# Adafruit_MicroUSB_Lipo.net
KiCad netlist of a schematic drawn in EAGLE
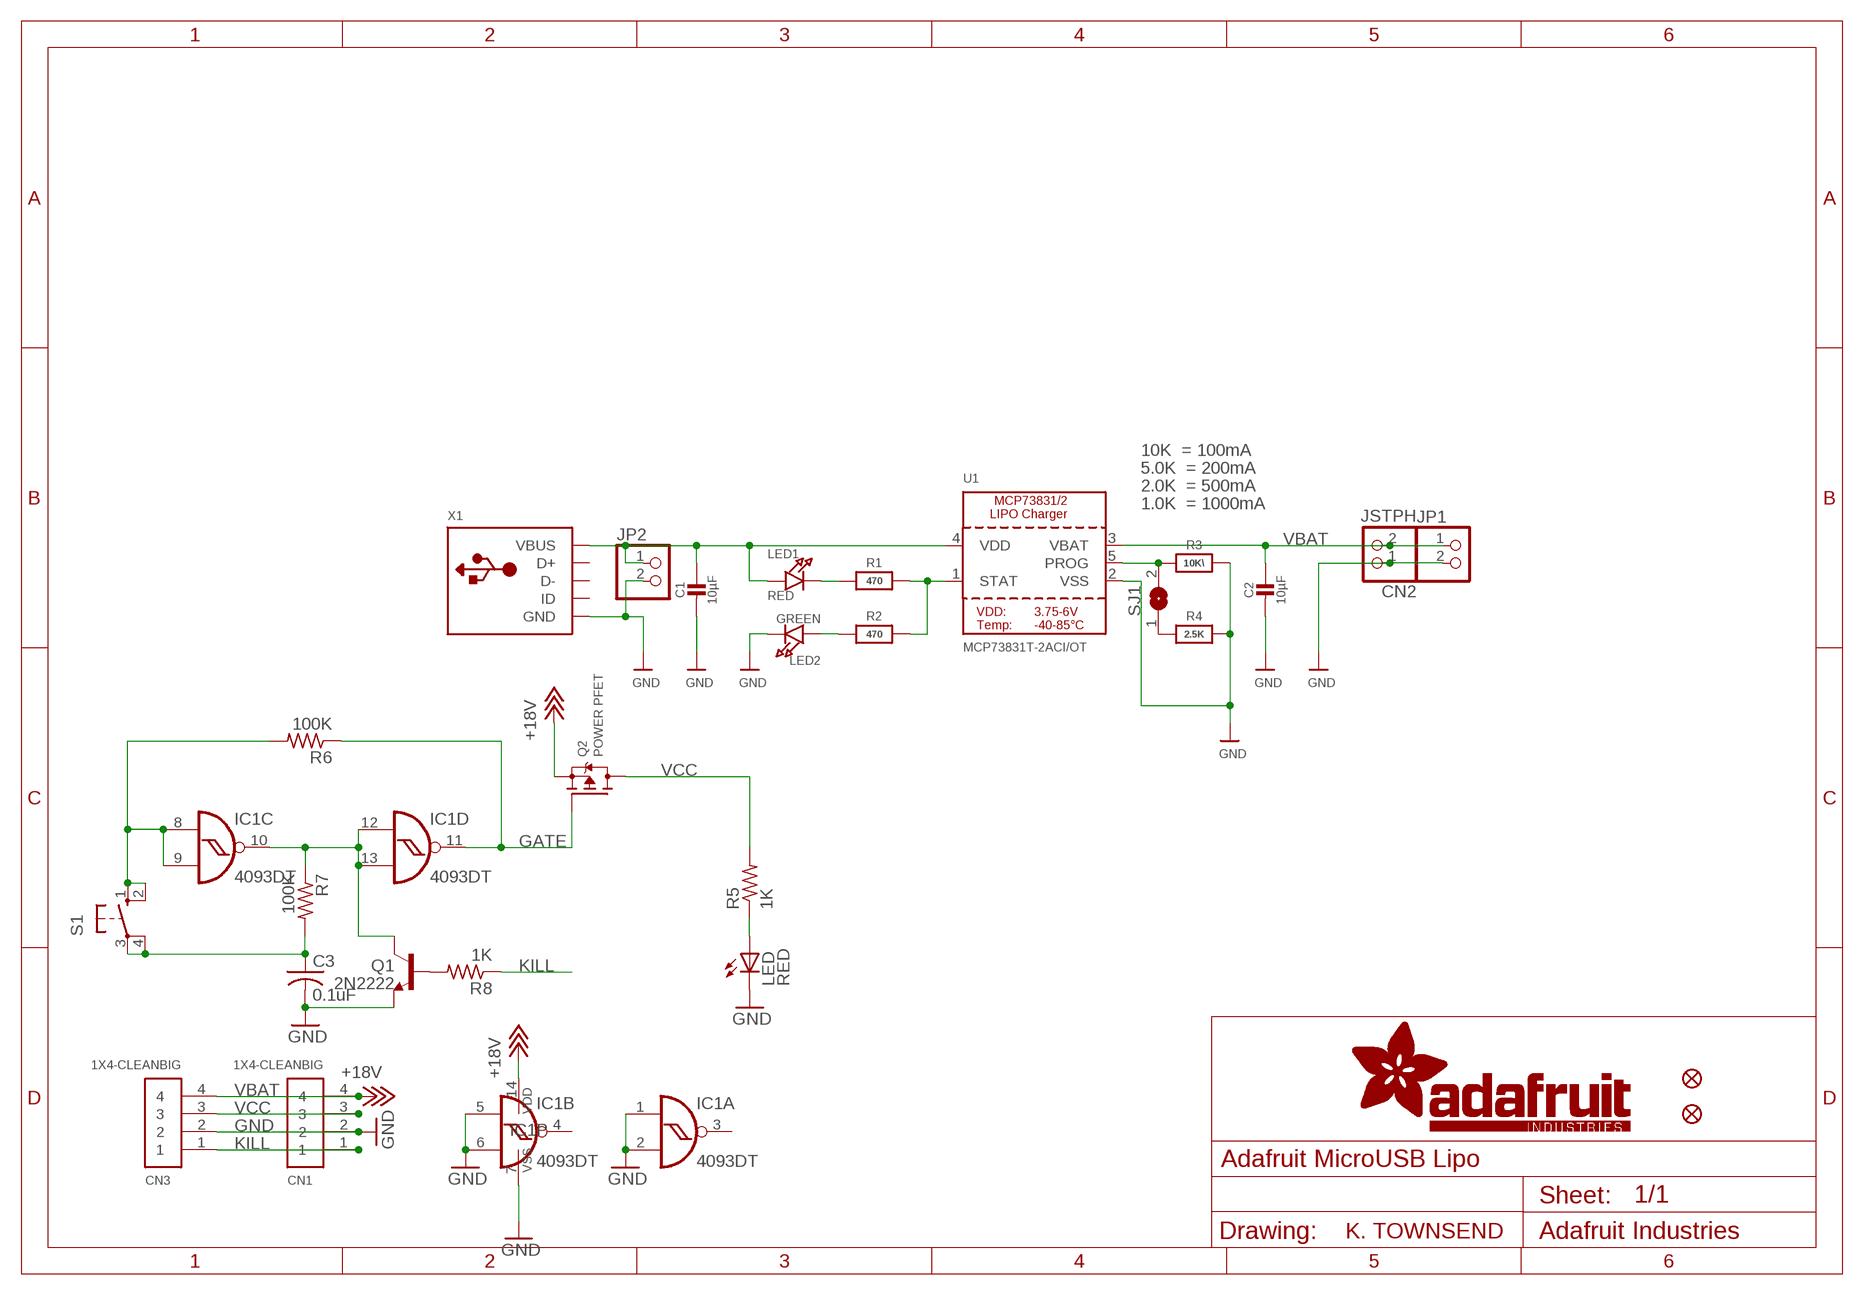
[diagram p0: schematic, sheet 1]

(export (version "E")
  (design (tool "Eeschema 10.0.6"))
  (components
    (comp (ref "C1")
      (value "10µF")
      (footprint "eagle-import:0805-NO")
      (libsource (lib "eagle-import") (part "CAP_CERAMIC0805-NOOUTLINE"))
    )
    (comp (ref "C2")
      (value "10µF")
      (footprint "eagle-import:0805-NO")
      (libsource (lib "eagle-import") (part "CAP_CERAMIC0805-NOOUTLINE"))
    )
    (comp (ref "C3")
      (value "0.1uF")
      (footprint "eagle-import:C0805")
      (libsource (lib "eagle-import") (part "C-USC0805"))
    )
    (comp (ref "CN1")
      (value "1X4-CLEANBIG")
      (footprint "eagle-import:1X04-CLEANBIG")
      (libsource (lib "eagle-import") (part "1X4-CLEANBIG"))
    )
    (comp (ref "CN2")
      (value "JSTPH")
      (footprint "eagle-import:JSTPH2")
      (libsource (lib "eagle-import") (part "JST_2PIN"))
    )
    (comp (ref "CN3")
      (value "1X4-CLEANBIG")
      (footprint "eagle-import:1X04-CLEANBIG")
      (libsource (lib "eagle-import") (part "1X4-CLEANBIG"))
    )
    (comp (ref "FID1")
      (value "FIDUCIAL\"\"")
      (footprint "eagle-import:FIDUCIAL_1MM")
      (libsource (lib "eagle-import") (part "FIDUCIAL{dblquote}{dblquote}"))
    )
    (comp (ref "FID2")
      (value "FIDUCIAL\"\"")
      (footprint "eagle-import:FIDUCIAL_1MM")
      (fields (field (name "BOM") "EXCLUDE"))
      (libsource (lib "eagle-import") (part "FIDUCIAL{dblquote}{dblquote}"))
    )
    (comp (ref "IC1")
      (value "4093DT")
      (footprint "eagle-import:MC14093B-TSSOP14")
      (libsource (lib "eagle-import") (part "4093DT"))
    )
    (comp (ref "JP1")
      (value "HEADER-1X2ROUND")
      (footprint "eagle-import:1X02_ROUND")
      (libsource (lib "eagle-import") (part "HEADER-1X2ROUND"))
    )
    (comp (ref "JP2")
      (value "HEADER-1X2ROUND")
      (footprint "eagle-import:1X02_ROUND")
      (libsource (lib "eagle-import") (part "HEADER-1X2ROUND"))
    )
    (comp (ref "LED")
      (value "RED")
      (footprint "eagle-import:CHIP-LED0805")
      (libsource (lib "eagle-import") (part "LEDCHIP-LED0805"))
    )
    (comp (ref "LED1")
      (value "RED")
      (footprint "eagle-import:CHIPLED_0805_NOOUTLINE")
      (libsource (lib "eagle-import") (part "LED0805_NOOUTLINE"))
    )
    (comp (ref "LED2")
      (value "GREEN")
      (footprint "eagle-import:CHIPLED_0805_NOOUTLINE")
      (libsource (lib "eagle-import") (part "LED0805_NOOUTLINE"))
    )
    (comp (ref "Q1")
      (value "2N2222")
      (footprint "eagle-import:SOT23-BEC")
      (libsource (lib "eagle-import") (part "-NPN-SOT23-BECMMBT2222ALT1"))
    )
    (comp (ref "Q2")
      (value "POWER PFET")
      (footprint "eagle-import:SOT23-WIDE")
      (libsource (lib "eagle-import") (part "MOSFET-PWIDE"))
    )
    (comp (ref "R1")
      (value "470")
      (footprint "eagle-import:0805-NO")
      (libsource (lib "eagle-import") (part "RESISTOR0805_NOOUTLINE"))
    )
    (comp (ref "R2")
      (value "470")
      (footprint "eagle-import:0805-NO")
      (libsource (lib "eagle-import") (part "RESISTOR0805_NOOUTLINE"))
    )
    (comp (ref "R3")
      (value "10K\\")
      (footprint "eagle-import:0805-NO")
      (libsource (lib "eagle-import") (part "RESISTOR0805_NOOUTLINE"))
    )
    (comp (ref "R4")
      (value "2.5K")
      (footprint "eagle-import:0805-NO")
      (libsource (lib "eagle-import") (part "RESISTOR0805_NOOUTLINE"))
    )
    (comp (ref "R5")
      (value "1K")
      (footprint "eagle-import:R0805")
      (libsource (lib "eagle-import") (part "rcl_R-US_R0805"))
    )
    (comp (ref "R6")
      (value "100K")
      (footprint "eagle-import:R0805")
      (libsource (lib "eagle-import") (part "rcl_R-US_R0805"))
    )
    (comp (ref "R7")
      (value "100K")
      (footprint "eagle-import:R0805")
      (libsource (lib "eagle-import") (part "rcl_R-US_R0805"))
    )
    (comp (ref "R8")
      (value "1K")
      (footprint "eagle-import:R0805")
      (libsource (lib "eagle-import") (part "R-US_R0805"))
    )
    (comp (ref "S1")
      (value "40-XX-ROUND")
      (footprint "eagle-import:B3F-40XX-ROUND")
      (libsource (lib "eagle-import") (part "40-XX-ROUND"))
    )
    (comp (ref "SJ1")
      (value "SOLDERJUMPER")
      (footprint "eagle-import:SOLDERJUMPER_ARROW_NOPASTE")
      (libsource (lib "eagle-import") (part "SOLDERJUMPER"))
    )
    (comp (ref "U1")
      (value "MCP73831T-2ACI/OT")
      (footprint "eagle-import:SOT23-5")
      (libsource (lib "eagle-import") (part "MCP73831/2"))
    )
    (comp (ref "X1")
      (value "USBMICRO_20329")
      (footprint "eagle-import:4UCONN_20329")
      (libsource (lib "eagle-import") (part "USBMICRO_20329"))
    )
  )
  (nets
    (net (code "1") (name "+18V") (class "Default")
      (node (ref "C2") (pin "1") (pinfunction "1_1") (pintype "passive"))
      (node (ref "CN1") (pin "4") (pinfunction "4_4") (pintype "bidirectional"))
      (node (ref "CN2") (pin "2") (pinfunction "2_2") (pintype "passive"))
      (node (ref "CN3") (pin "4") (pinfunction "4_4") (pintype "bidirectional"))
      (node (ref "IC1") (pin "14") (pinfunction "VDD_14") (pintype "power_in"))
      (node (ref "JP1") (pin "1") (pinfunction "1_1") (pintype "passive"))
      (node (ref "Q2") (pin "2") (pinfunction "S_2") (pintype "passive"))
      (node (ref "U1") (pin "3") (pinfunction "VBAT_3") (pintype "power_in"))
    )
    (net (code "2") (name "/GATE") (class "Default")
      (node (ref "IC1") (pin "11") (pinfunction "O_11") (pintype "output"))
      (node (ref "Q2") (pin "1") (pinfunction "G_1") (pintype "passive"))
      (node (ref "R6") (pin "1") (pinfunction "1_1") (pintype "passive"))
    )
    (net (code "3") (name "/KILL") (class "Default")
      (node (ref "CN1") (pin "1") (pinfunction "1_1") (pintype "bidirectional"))
      (node (ref "CN3") (pin "1") (pinfunction "1_1") (pintype "bidirectional"))
      (node (ref "R8") (pin "1") (pinfunction "1_1") (pintype "passive"))
    )
    (net (code "4") (name "/VCC") (class "Default")
      (node (ref "CN1") (pin "3") (pinfunction "3_3") (pintype "bidirectional"))
      (node (ref "CN3") (pin "3") (pinfunction "3_3") (pintype "bidirectional"))
      (node (ref "Q2") (pin "3") (pinfunction "D_3") (pintype "passive"))
      (node (ref "R5") (pin "2") (pinfunction "2_2") (pintype "passive"))
    )
    (net (code "5") (name "GND") (class "Default")
      (node (ref "C1") (pin "2") (pinfunction "2_2") (pintype "passive"))
      (node (ref "C2") (pin "2") (pinfunction "2_2") (pintype "passive"))
      (node (ref "C3") (pin "2") (pinfunction "2_2") (pintype "passive"))
      (node (ref "CN1") (pin "2") (pinfunction "2_2") (pintype "bidirectional"))
      (node (ref "CN2") (pin "1") (pinfunction "1_1") (pintype "passive"))
      (node (ref "CN3") (pin "2") (pinfunction "2_2") (pintype "bidirectional"))
      (node (ref "IC1") (pin "1") (pinfunction "I0_1") (pintype "input"))
      (node (ref "IC1") (pin "2") (pinfunction "I1_2") (pintype "input"))
      (node (ref "IC1") (pin "5") (pinfunction "I0_5") (pintype "input"))
      (node (ref "IC1") (pin "6") (pinfunction "I1_6") (pintype "input"))
      (node (ref "IC1") (pin "7") (pinfunction "VSS_7") (pintype "power_in"))
      (node (ref "JP1") (pin "2") (pinfunction "2_2") (pintype "passive"))
      (node (ref "JP2") (pin "2") (pinfunction "2_2") (pintype "passive"))
      (node (ref "LED") (pin "C") (pinfunction "C_C") (pintype "passive"))
      (node (ref "LED2") (pin "C") (pinfunction "C_C") (pintype "passive"))
      (node (ref "Q1") (pin "E") (pinfunction "E_E") (pintype "passive"))
      (node (ref "R3") (pin "2") (pinfunction "2_2") (pintype "passive"))
      (node (ref "R4") (pin "2") (pinfunction "2_2") (pintype "passive"))
      (node (ref "U1") (pin "2") (pinfunction "VSS_2") (pintype "power_in"))
      (node (ref "X1") (pin "BASE@1") (pinfunction "GND_BASE@1") (pintype "power_in"))
      (node (ref "X1") (pin "BASE@2") (pinfunction "GND_BASE@2") (pintype "power_in"))
      (node (ref "X1") (pin "GND") (pinfunction "GND_GND") (pintype "power_in"))
      (node (ref "X1") (pin "SPRT@1") (pinfunction "GND_SPRT@1") (pintype "power_in"))
      (node (ref "X1") (pin "SPRT@2") (pinfunction "GND_SPRT@2") (pintype "power_in"))
      (node (ref "X1") (pin "SPRT@3") (pinfunction "GND_SPRT@3") (pintype "power_in"))
      (node (ref "X1") (pin "SPRT@4") (pinfunction "GND_SPRT@4") (pintype "power_in"))
    )
    (net (code "6") (name "Net-(IC1C-I0)") (class "Default")
      (node (ref "IC1") (pin "8") (pinfunction "I0_8") (pintype "input"))
      (node (ref "IC1") (pin "9") (pinfunction "I1_9") (pintype "input"))
      (node (ref "R6") (pin "2") (pinfunction "2_2") (pintype "passive"))
      (node (ref "S1") (pin "1") (pinfunction "S_1") (pintype "passive"))
      (node (ref "S1") (pin "2") (pinfunction "S1_2") (pintype "passive"))
    )
    (net (code "7") (name "Net-(IC1C-O)") (class "Default")
      (node (ref "IC1") (pin "10") (pinfunction "O_10") (pintype "output"))
      (node (ref "IC1") (pin "12") (pinfunction "I0_12") (pintype "input"))
      (node (ref "IC1") (pin "13") (pinfunction "I1_13") (pintype "input"))
      (node (ref "Q1") (pin "C") (pinfunction "C_C") (pintype "passive"))
      (node (ref "R7") (pin "1") (pinfunction "1_1") (pintype "passive"))
    )
    (net (code "8") (name "Net-(LED-PadA)") (class "Default")
      (node (ref "LED") (pin "A") (pinfunction "A_A") (pintype "passive"))
      (node (ref "R5") (pin "1") (pinfunction "1_1") (pintype "passive"))
    )
    (net (code "9") (name "Net-(LED1-PadC)") (class "Default")
      (node (ref "LED1") (pin "C") (pinfunction "C_C") (pintype "passive"))
      (node (ref "R1") (pin "1") (pinfunction "1_1") (pintype "passive"))
    )
    (net (code "10") (name "Net-(LED2-PadA)") (class "Default")
      (node (ref "LED2") (pin "A") (pinfunction "A_A") (pintype "passive"))
      (node (ref "R2") (pin "1") (pinfunction "1_1") (pintype "passive"))
    )
    (net (code "11") (name "Net-(Q1-PadB)") (class "Default")
      (node (ref "Q1") (pin "B") (pinfunction "B_B") (pintype "passive"))
      (node (ref "R8") (pin "2") (pinfunction "2_2") (pintype "passive"))
    )
    (net (code "12") (name "Net-(R4-Pad1)") (class "Default")
      (node (ref "R4") (pin "1") (pinfunction "1_1") (pintype "passive"))
      (node (ref "SJ1") (pin "1") (pinfunction "1_1") (pintype "passive"))
    )
    (net (code "13") (name "Net-(S1-P)") (class "Default")
      (node (ref "C3") (pin "1") (pinfunction "1_1") (pintype "passive"))
      (node (ref "R7") (pin "2") (pinfunction "2_2") (pintype "passive"))
      (node (ref "S1") (pin "3") (pinfunction "P_3") (pintype "passive"))
      (node (ref "S1") (pin "4") (pinfunction "P1_4") (pintype "passive"))
    )
    (net (code "14") (name "Net-(U1-PROG)") (class "Default")
      (node (ref "R3") (pin "1") (pinfunction "1_1") (pintype "passive"))
      (node (ref "SJ1") (pin "2") (pinfunction "2_2") (pintype "passive"))
      (node (ref "U1") (pin "5") (pinfunction "PROG_5") (pintype "input"))
    )
    (net (code "15") (name "Net-(U1-STAT)") (class "Default")
      (node (ref "R1") (pin "2") (pinfunction "2_2") (pintype "passive"))
      (node (ref "R2") (pin "2") (pinfunction "2_2") (pintype "passive"))
      (node (ref "U1") (pin "1") (pinfunction "STAT_1") (pintype "output"))
    )
    (net (code "16") (name "Net-(U1-VDD)") (class "Default")
      (node (ref "C1") (pin "1") (pinfunction "1_1") (pintype "passive"))
      (node (ref "JP2") (pin "1") (pinfunction "1_1") (pintype "passive"))
      (node (ref "LED1") (pin "A") (pinfunction "A_A") (pintype "passive"))
      (node (ref "U1") (pin "4") (pinfunction "VDD_4") (pintype "power_in"))
      (node (ref "X1") (pin "VBUS") (pinfunction "VBUS_VBUS") (pintype "power_in"))
    )
    (net (code "17") (name "unconnected-(IC1A-O-Pad3)") (class "Default")
      (node (ref "IC1") (pin "3") (pinfunction "O_3") (pintype "output"))
    )
    (net (code "18") (name "unconnected-(IC1B-O-Pad4)") (class "Default")
      (node (ref "IC1") (pin "4") (pinfunction "O_4") (pintype "output"))
    )
    (net (code "19") (name "unconnected-(X1-PadD+)") (class "Default")
      (node (ref "X1") (pin "D+") (pinfunction "D+_D+") (pintype "bidirectional"))
    )
    (net (code "20") (name "unconnected-(X1-PadD-)") (class "Default")
      (node (ref "X1") (pin "D-") (pinfunction "D-_D-") (pintype "bidirectional"))
    )
    (net (code "21") (name "unconnected-(X1-PadID)") (class "Default")
      (node (ref "X1") (pin "ID") (pinfunction "ID_ID") (pintype "bidirectional"))
    )
  )
)
